# attinier85-motherboard-pth-mk-1_0.net
KiCad netlist of a schematic drawn in EAGLE
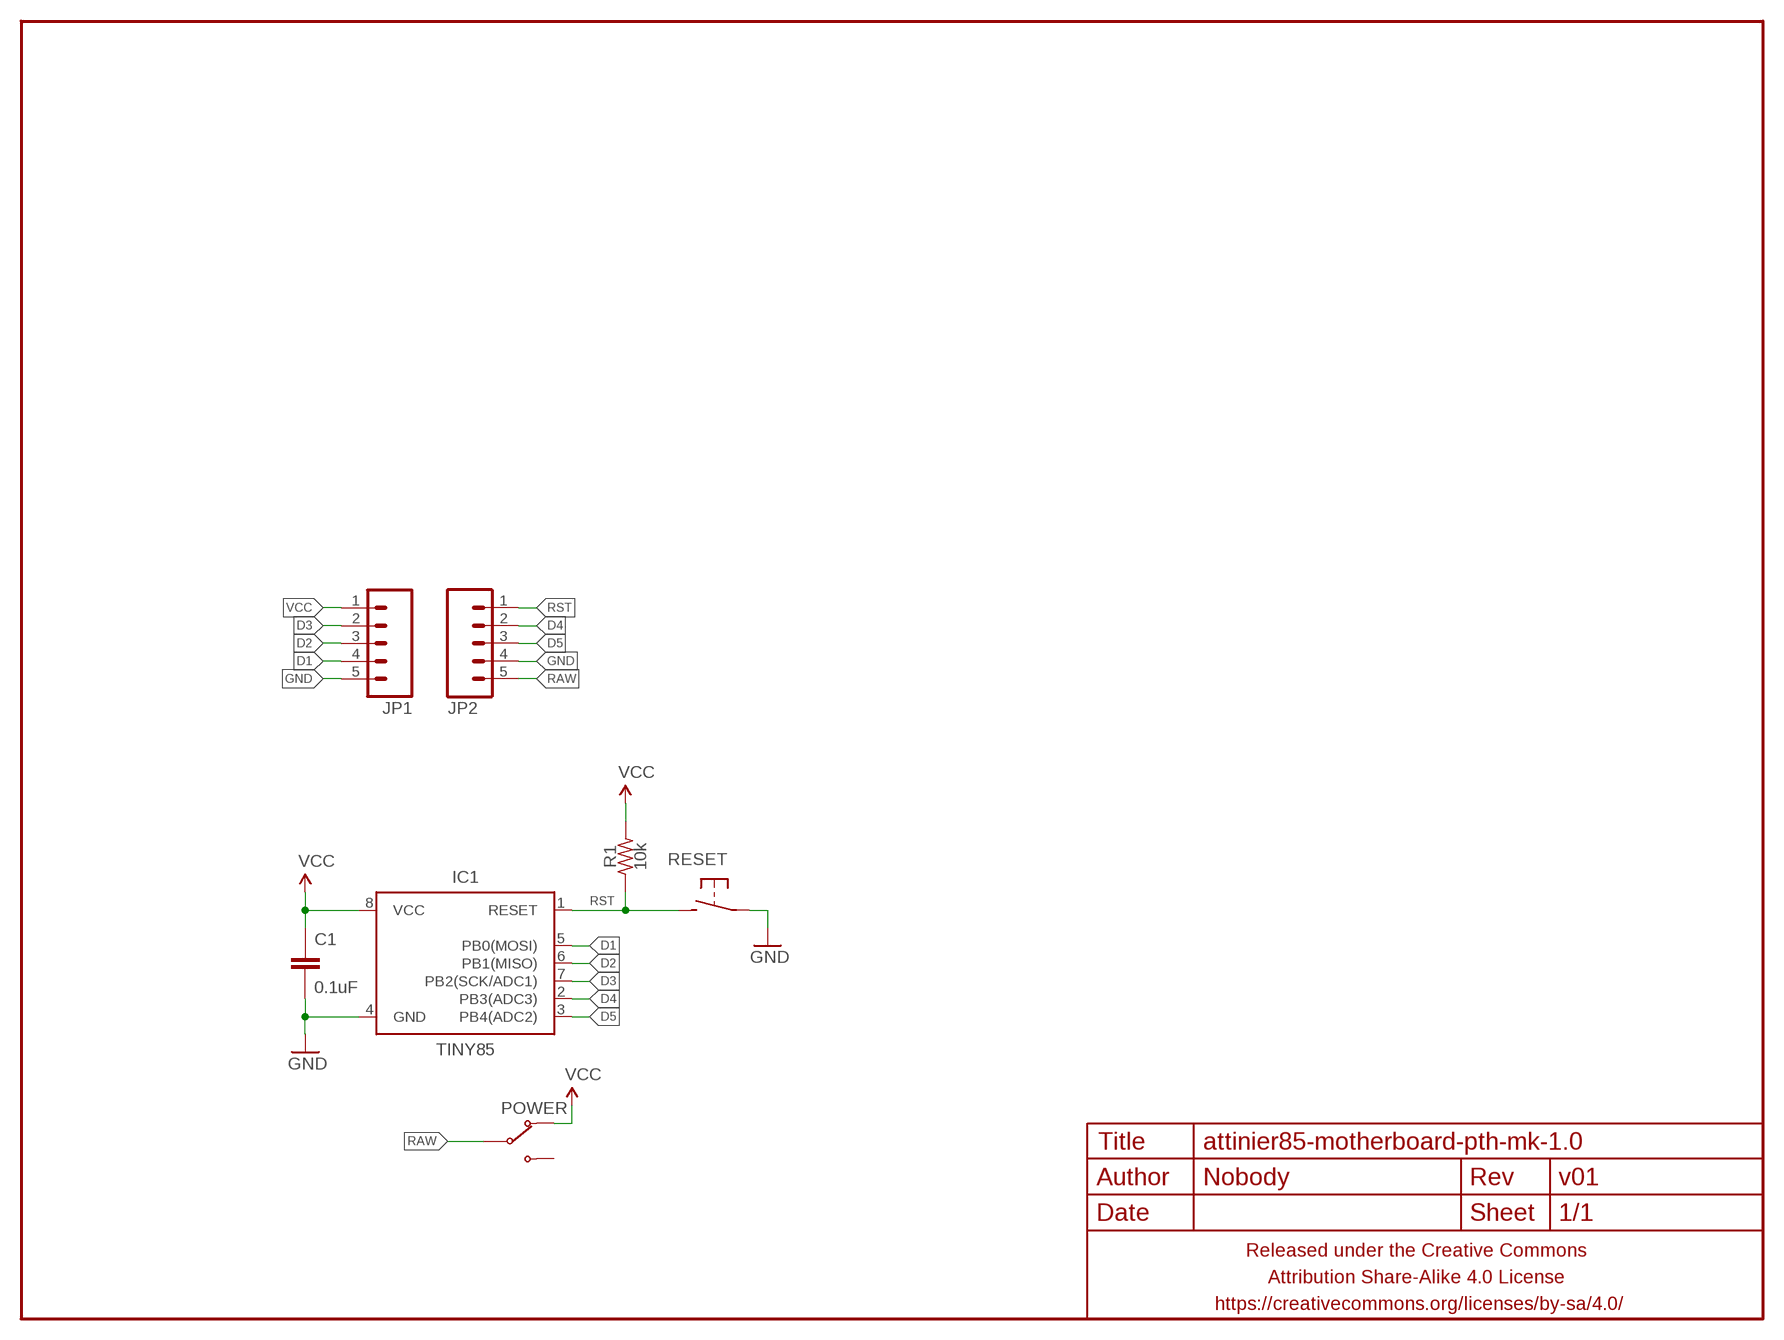
[diagram p0: schematic, sheet 1]

(export (version "E")
  (design (tool "Eeschema 10.0.6"))
  (components
    (comp (ref "C1")
      (value "0.1uF")
      (footprint "eagle-import:C025-024X044")
      (libsource (lib "eagle-import") (part "CAPACITOR-CERAMIC025-024X044"))
    )
    (comp (ref "FRAME1")
      (value "FRAME-LETTERNO_PACKAGE")
      (footprint "eagle-import:DUMMY")
      (fields (field (name "DESIGNER") "Nobody"))
      (libsource (lib "eagle-import") (part "FRAME-LETTERNO_PACKAGE"))
    )
    (comp (ref "IC1")
      (value "TINY85")
      (footprint "eagle-import:DIP08")
      (libsource (lib "eagle-import") (part "ATTINY45TINY85-20-DIP"))
    )
    (comp (ref "JP1")
      (value "M05PTH")
      (footprint "eagle-import:1X05")
      (libsource (lib "eagle-import") (part "M05PTH"))
    )
    (comp (ref "JP2")
      (value "M05PTH")
      (footprint "eagle-import:1X05")
      (libsource (lib "eagle-import") (part "M05PTH"))
    )
    (comp (ref "POWER")
      (value "SWITCH-SPDTPTH-RA-2.54MM")
      (footprint "eagle-import:SPDT-RA-2.54MM")
      (libsource (lib "eagle-import") (part "SWITCH-SPDTPTH-RA-2.54MM"))
    )
    (comp (ref "R1")
      (value "10k")
      (footprint "eagle-import:RESISTOR-AXIAL-PTH-7.62MM")
      (libsource (lib "eagle-import") (part "RESISTORPTH-AXIAL-7.62MM"))
    )
    (comp (ref "RESET")
      (value "DTS-6MM")
      (footprint "eagle-import:TACTILE-PTH-SIDE")
      (libsource (lib "eagle-import") (part "SPST-NO-TACT3MM-RA"))
    )
  )
  (nets
    (net (code "1") (name "D1") (class "Default")
      (node (ref "IC1") (pin "5") (pinfunction "PB0(MOSI)_5") (pintype "bidirectional"))
      (node (ref "JP1") (pin "4") (pinfunction "4_4") (pintype "passive"))
    )
    (net (code "2") (name "D2") (class "Default")
      (node (ref "IC1") (pin "6") (pinfunction "PB1(MISO)_6") (pintype "bidirectional"))
      (node (ref "JP1") (pin "3") (pinfunction "3_3") (pintype "passive"))
    )
    (net (code "3") (name "D3") (class "Default")
      (node (ref "IC1") (pin "7") (pinfunction "PB2(SCK/ADC1)_7") (pintype "bidirectional"))
      (node (ref "JP1") (pin "2") (pinfunction "2_2") (pintype "passive"))
    )
    (net (code "4") (name "D4") (class "Default")
      (node (ref "IC1") (pin "2") (pinfunction "PB3(ADC3)_2") (pintype "bidirectional"))
      (node (ref "JP2") (pin "2") (pinfunction "2_2") (pintype "passive"))
    )
    (net (code "5") (name "D5") (class "Default")
      (node (ref "IC1") (pin "3") (pinfunction "PB4(ADC2)_3") (pintype "bidirectional"))
      (node (ref "JP2") (pin "3") (pinfunction "3_3") (pintype "passive"))
    )
    (net (code "6") (name "GND") (class "Default")
      (node (ref "C1") (pin "2") (pinfunction "2_2") (pintype "passive"))
      (node (ref "IC1") (pin "4") (pinfunction "GND_4") (pintype "bidirectional"))
      (node (ref "JP1") (pin "5") (pinfunction "5_5") (pintype "passive"))
      (node (ref "JP2") (pin "4") (pinfunction "4_4") (pintype "passive"))
      (node (ref "RESET") (pin "1") (pinfunction "1_1") (pintype "passive"))
    )
    (net (code "7") (name "RAW") (class "Default")
      (node (ref "JP2") (pin "5") (pinfunction "5_5") (pintype "passive"))
      (node (ref "POWER") (pin "2") (pinfunction "COM_2") (pintype "passive"))
    )
    (net (code "8") (name "RST") (class "Default")
      (node (ref "IC1") (pin "1") (pinfunction "RESET_1") (pintype "bidirectional"))
      (node (ref "JP2") (pin "1") (pinfunction "1_1") (pintype "passive"))
      (node (ref "R1") (pin "P$1") (pinfunction "1_P$1") (pintype "passive"))
      (node (ref "RESET") (pin "2") (pinfunction "2_2") (pintype "passive"))
    )
    (net (code "9") (name "VCC") (class "Default")
      (node (ref "C1") (pin "1") (pinfunction "1_1") (pintype "passive"))
      (node (ref "IC1") (pin "8") (pinfunction "VCC_8") (pintype "bidirectional"))
      (node (ref "JP1") (pin "1") (pinfunction "1_1") (pintype "passive"))
      (node (ref "POWER") (pin "1") (pinfunction "NC_1") (pintype "passive"))
      (node (ref "R1") (pin "P$2") (pinfunction "2_P$2") (pintype "passive"))
    )
    (net (code "10") (name "unconnected-(POWER-NO-Pad3)") (class "Default")
      (node (ref "POWER") (pin "3") (pinfunction "NO_3") (pintype "passive"))
    )
  )
)
